# BLDC_MC_Schematic.net
KiCad netlist of a schematic drawn in Altium Designer
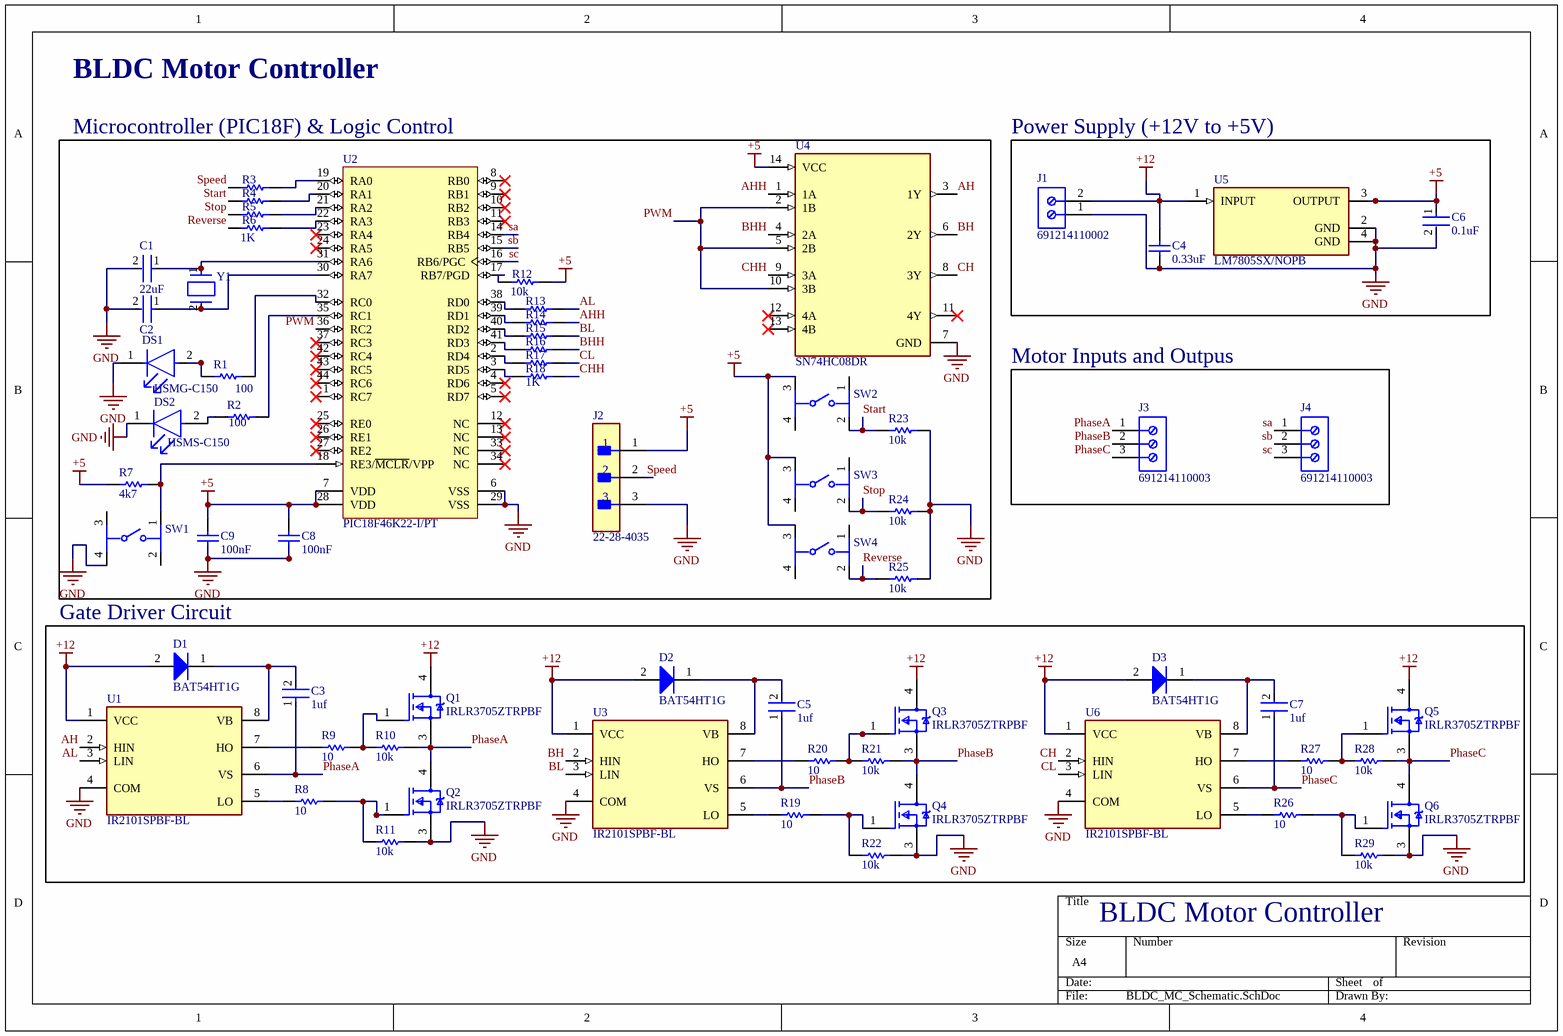
[diagram p0: BLDC_MC_Schematic.SchDoc]

(export (version "E")
  (design (tool "Eeschema 10.0.6"))
  (components
    (comp (ref "C1")
      (value "22uF")
      (footprint "FP-GRM21B-0_15-MFG")
      (description "Chip Multilayer Ceramic Capacitors for General Purpose, 0805, 22uF, X5R, 15%, 20%, 6.3V")
      (fields (field (name "VOLTAGE") "6.3V") (field (name "TOLERANCE") "20%"))
      (libsource (lib "Altium Content Vault") (part "b4654b650e69147ec39a6b967a45e02"))
    )
    (comp (ref "C2")
      (value "22uF")
      (footprint "FP-GRM21B-0_15-MFG")
      (description "Chip Multilayer Ceramic Capacitors for General Purpose, 0805, 22uF, X5R, 15%, 20%, 6.3V")
      (fields (field (name "VOLTAGE") "6.3V") (field (name "TOLERANCE") "20%"))
      (libsource (lib "Altium Content Vault") (part "b4654b650e69147ec39a6b967a45e02"))
    )
    (comp (ref "C3")
      (value "1uf")
      (footprint "FP-GRM55D-0_4-IPC_A")
      (description "Chip Multilayer Ceramic Capacitors for General Purpose, 2220, 1.0uF, X7R, 15%, 10%, 250V")
      (fields (field (name "VOLTAGE") "250V") (field (name "TOLERANCE") "10%"))
      (libsource (lib "Altium Content Vault") (part "b4654b650e69147ec39a6b967a45e02"))
    )
    (comp (ref "C4")
      (value "0.33uF")
      (footprint "CAPC1005X55X25ML05T10")
      (fields (field (name "PART NUMBER") "GRM155R61A334KE15D") (field (name "MANUFACTURER") "Murata"))
      (libsource (lib "Altium Content Vault") (part "CAP"))
    )
    (comp (ref "C5")
      (value "1uf")
      (footprint "FP-GRM55D-0_4-IPC_A")
      (description "Chip Multilayer Ceramic Capacitors for General Purpose, 2220, 1.0uF, X7R, 15%, 10%, 250V")
      (fields (field (name "VOLTAGE") "250V") (field (name "TOLERANCE") "10%"))
      (libsource (lib "Altium Content Vault") (part "b4654b650e69147ec39a6b967a45e02"))
    )
    (comp (ref "C6")
      (value "0.1uF")
      (footprint "FP-C1005-050-0_05-IPC_C")
      (description "Multilayer Ceramic Capacitors 100nF ±10% 50V X7R SMD 0402")
      (fields (field (name "VOLTAGE") "50V") (field (name "TOLERANCE") "10%"))
      (libsource (lib "Altium Content Vault") (part "b4654b650e69147ec39a6b967a45e02"))
    )
    (comp (ref "C7")
      (value "1uf")
      (footprint "FP-GRM55D-0_4-IPC_A")
      (description "Chip Multilayer Ceramic Capacitors for General Purpose, 2220, 1.0uF, X7R, 15%, 10%, 250V")
      (fields (field (name "VOLTAGE") "250V") (field (name "TOLERANCE") "10%"))
      (libsource (lib "Altium Content Vault") (part "b4654b650e69147ec39a6b967a45e02"))
    )
    (comp (ref "C8")
      (value "100nF")
      (footprint "CAPC1005X56X25ML10T15")
      (fields
        (field (name "MANUFACTURER") "AVX Interconnect / Elco")
        (field (name "PART NUMBER") "0402YG104ZAT2A")
      )
      (libsource (lib "Altium Content Vault") (part "CAP"))
    )
    (comp (ref "C9")
      (value "100nF")
      (footprint "CAPC1005X56X25ML10T15")
      (fields
        (field (name "MANUFACTURER") "AVX Interconnect / Elco")
        (field (name "PART NUMBER") "0402YG104ZAT2A")
      )
      (libsource (lib "Altium Content Vault") (part "CAP"))
    )
    (comp (ref "D1")
      (value "BAT54HT1G")
      (footprint "ONSC-SOD-323-2-477-02_V")
      (description "Schottky Barrier Diode, 2-Pin SOD-323, Pb-Free, Tape and Reel")
      (fields (field (name "MANUFACTURER") "On Semiconductor"))
      (libsource (lib "Altium Content Vault") (part "ONSC-D-K1A2-2"))
    )
    (comp (ref "D2")
      (value "BAT54HT1G")
      (footprint "ONSC-SOD-323-2-477-02_V")
      (description "Schottky Barrier Diode, 2-Pin SOD-323, Pb-Free, Tape and Reel")
      (fields (field (name "MANUFACTURER") "On Semiconductor"))
      (libsource (lib "Altium Content Vault") (part "ONSC-D-K1A2-2"))
    )
    (comp (ref "D3")
      (value "BAT54HT1G")
      (footprint "ONSC-SOD-323-2-477-02_V")
      (description "Schottky Barrier Diode, 2-Pin SOD-323, Pb-Free, Tape and Reel")
      (fields (field (name "MANUFACTURER") "On Semiconductor"))
      (libsource (lib "Altium Content Vault") (part "ONSC-D-K1A2-2"))
    )
    (comp (ref "DS1")
      (value "HSMG-C150")
      (footprint "FP-HSMG-C150-MFG")
      (description "LED GREEN DIFFUSED 1206 SMD")
      (fields
        (field (name "MANUFACTURER") "Broadcom")
        (field (name "OCTOPART") "https://octopart.com/hsmg-c150-broadcom-71131304")
      )
      (libsource (lib "Altium Content Vault") (part "8706943c75ba83719d021d2fdc84c58"))
    )
    (comp (ref "DS2")
      (value "HSMS-C150")
      (footprint "FP-HSMS-C150-MFG")
      (description "LED RED DIFFUSED CHIP SMD")
      (libsource (lib "Altium Content Vault") (part "8706943c75ba83719d021d2fdc84c58"))
    )
    (comp (ref "J1")
      (value "691214110002")
      (footprint "691214110002")
      (fields (field (name "VOLTAGE") "300V"))
      (libsource (lib "Altium Content Vault") (part "TBL - 1R - 02P - Screw"))
    )
    (comp (ref "J2")
      (value "22-28-4035")
      (footprint "FP-22-28-4035-MFG")
      (libsource (lib "Altium Content Vault") (part "0d3f023dd272f625e17a2be33dea85f"))
    )
    (comp (ref "J3")
      (value "691214110003")
      (footprint "691214110003")
      (fields (field (name "VOLTAGE") "300V"))
      (libsource (lib "Altium Content Vault") (part "TBL - 1R - 03P - Screw"))
    )
    (comp (ref "J4")
      (value "691214110003")
      (footprint "691214110003")
      (fields (field (name "VOLTAGE") "300V"))
      (libsource (lib "Altium Content Vault") (part "TBL - 1R - 03P - Screw"))
    )
    (comp (ref "Q1")
      (value "IRLR3705ZTRPBF")
      (footprint "FP-PG-TO252-3-MFG")
      (description "MOSFET N-CH 55V 42A DPAK")
      (fields (field (name "OCTOPART") "https://octopart.com/irlr3705ztrpbf-infineon-65875040"))
      (libsource (lib "Altium Content Vault") (part "e748bc7c0bda14637a9f13d1d571a93"))
    )
    (comp (ref "Q2")
      (value "IRLR3705ZTRPBF")
      (footprint "FP-PG-TO252-3-MFG")
      (description "MOSFET N-CH 55V 42A DPAK")
      (fields (field (name "OCTOPART") "https://octopart.com/irlr3705ztrpbf-infineon-65875040"))
      (libsource (lib "Altium Content Vault") (part "e748bc7c0bda14637a9f13d1d571a93"))
    )
    (comp (ref "Q3")
      (value "IRLR3705ZTRPBF")
      (footprint "FP-PG-TO252-3-MFG")
      (description "MOSFET N-CH 55V 42A DPAK")
      (fields (field (name "OCTOPART") "https://octopart.com/irlr3705ztrpbf-infineon-65875040"))
      (libsource (lib "Altium Content Vault") (part "e748bc7c0bda14637a9f13d1d571a93"))
    )
    (comp (ref "Q4")
      (value "IRLR3705ZTRPBF")
      (footprint "FP-PG-TO252-3-MFG")
      (description "MOSFET N-CH 55V 42A DPAK")
      (fields (field (name "OCTOPART") "https://octopart.com/irlr3705ztrpbf-infineon-65875040"))
      (libsource (lib "Altium Content Vault") (part "e748bc7c0bda14637a9f13d1d571a93"))
    )
    (comp (ref "Q5")
      (value "IRLR3705ZTRPBF")
      (footprint "FP-PG-TO252-3-MFG")
      (description "MOSFET N-CH 55V 42A DPAK")
      (fields (field (name "OCTOPART") "https://octopart.com/irlr3705ztrpbf-infineon-65875040"))
      (libsource (lib "Altium Content Vault") (part "e748bc7c0bda14637a9f13d1d571a93"))
    )
    (comp (ref "Q6")
      (value "IRLR3705ZTRPBF")
      (footprint "FP-PG-TO252-3-MFG")
      (description "MOSFET N-CH 55V 42A DPAK")
      (fields (field (name "OCTOPART") "https://octopart.com/irlr3705ztrpbf-infineon-65875040"))
      (libsource (lib "Altium Content Vault") (part "e748bc7c0bda14637a9f13d1d571a93"))
    )
    (comp (ref "R1")
      (value "100")
      (footprint "RESC1608X55X30LL15T15")
      (fields (field (name "MANUFACTURER") "Panasonic") (field (name "PART NUMBER") "ERJ-3EKF1000V"))
      (libsource (lib "Altium Content Vault") (part "RES"))
    )
    (comp (ref "R2")
      (value "100")
      (footprint "RESC1608X55X30LL15T15")
      (fields (field (name "MANUFACTURER") "Panasonic") (field (name "PART NUMBER") "ERJ-3EKF1000V"))
      (libsource (lib "Altium Content Vault") (part "RES"))
    )
    (comp (ref "R3")
      (value "1K")
      (footprint "RESC1608X55X30LL15T15")
      (fields (field (name "PART NUMBER") "ERJ-3EKF1001V") (field (name "MANUFACTURER") "Panasonic"))
      (libsource (lib "Altium Content Vault") (part "RES"))
    )
    (comp (ref "R4")
      (value "1K")
      (footprint "RESC1608X55X30LL15T15")
      (fields (field (name "PART NUMBER") "ERJ-3EKF1001V") (field (name "MANUFACTURER") "Panasonic"))
      (libsource (lib "Altium Content Vault") (part "RES"))
    )
    (comp (ref "R5")
      (value "1K")
      (footprint "RESC1608X55X30LL15T15")
      (fields (field (name "PART NUMBER") "ERJ-3EKF1001V") (field (name "MANUFACTURER") "Panasonic"))
      (libsource (lib "Altium Content Vault") (part "RES"))
    )
    (comp (ref "R6")
      (value "1K")
      (footprint "RESC1608X55X30LL15T15")
      (fields (field (name "PART NUMBER") "ERJ-3EKF1001V") (field (name "MANUFACTURER") "Panasonic"))
      (libsource (lib "Altium Content Vault") (part "RES"))
    )
    (comp (ref "R7")
      (value "4k7")
      (footprint "RESC1005X40X25LL05T05")
      (description "Chip Resistor, 4.7 KOhm, +/- 1%, 0.1 W, -55 to 155 degC, 0402 (1005 Metric), RoHS, Tape and Reel")
      (fields (field (name "TOLERANCE") "1%") (field (name "PARTNUMBER") "ERJ-2RKF4701X"))
      (libsource (lib "Altium Content Vault") (part "RES-2"))
    )
    (comp (ref "R8")
      (value "10")
      (footprint "RESC2013X50X30NL20T20")
      (fields (field (name "MANUFACTURER") "Vishay Dale") (field (name "PART NUMBER") "CRCW080510R0FKEA"))
      (libsource (lib "Altium Content Vault") (part "RES"))
    )
    (comp (ref "R9")
      (value "10")
      (footprint "RESC2013X50X30NL20T20")
      (fields (field (name "MANUFACTURER") "Vishay Dale") (field (name "PART NUMBER") "CRCW080510R0FKEA"))
      (libsource (lib "Altium Content Vault") (part "RES"))
    )
    (comp (ref "R10")
      (value "10k")
      (footprint "RESC1609X50X30NL8T20")
      (description "Chip Resistor, 10 KOhm, +/- 1%, 100 mW, -55 to 155 degC, 0603 (1608 Metric), RoHS, Tape and Reel")
      (fields (field (name "MANUFACTURER") "Vishay Semiconductor"))
      (libsource (lib "Altium Content Vault") (part "RES-2"))
    )
    (comp (ref "R11")
      (value "10k")
      (footprint "RESC1609X50X30NL8T20")
      (description "Chip Resistor, 10 KOhm, +/- 1%, 100 mW, -55 to 155 degC, 0603 (1608 Metric), RoHS, Tape and Reel")
      (fields (field (name "MANUFACTURER") "Vishay Semiconductor"))
      (libsource (lib "Altium Content Vault") (part "RES-2"))
    )
    (comp (ref "R12")
      (value "10k")
      (footprint "RESC1609X50X30NL8T20")
      (description "Chip Resistor, 10 KOhm, +/- 1%, 100 mW, -55 to 155 degC, 0603 (1608 Metric), RoHS, Tape and Reel")
      (fields (field (name "MANUFACTURER") "Vishay Semiconductor"))
      (libsource (lib "Altium Content Vault") (part "RES-2"))
    )
    (comp (ref "R13")
      (value "1K")
      (footprint "RESC1608X55X30LL15T15")
      (fields (field (name "PART NUMBER") "ERJ-3EKF1001V") (field (name "MANUFACTURER") "Panasonic"))
      (libsource (lib "Altium Content Vault") (part "RES"))
    )
    (comp (ref "R14")
      (value "1K")
      (footprint "RESC1608X55X30LL15T15")
      (fields (field (name "PART NUMBER") "ERJ-3EKF1001V") (field (name "MANUFACTURER") "Panasonic"))
      (libsource (lib "Altium Content Vault") (part "RES"))
    )
    (comp (ref "R15")
      (value "1K")
      (footprint "RESC1608X55X30LL15T15")
      (fields (field (name "PART NUMBER") "ERJ-3EKF1001V") (field (name "MANUFACTURER") "Panasonic"))
      (libsource (lib "Altium Content Vault") (part "RES"))
    )
    (comp (ref "R16")
      (value "1K")
      (footprint "RESC1608X55X30LL15T15")
      (fields (field (name "PART NUMBER") "ERJ-3EKF1001V") (field (name "MANUFACTURER") "Panasonic"))
      (libsource (lib "Altium Content Vault") (part "RES"))
    )
    (comp (ref "R17")
      (value "1K")
      (footprint "RESC1608X55X30LL15T15")
      (fields (field (name "PART NUMBER") "ERJ-3EKF1001V") (field (name "MANUFACTURER") "Panasonic"))
      (libsource (lib "Altium Content Vault") (part "RES"))
    )
    (comp (ref "R18")
      (value "1K")
      (footprint "RESC1608X55X30LL15T15")
      (fields (field (name "PART NUMBER") "ERJ-3EKF1001V") (field (name "MANUFACTURER") "Panasonic"))
      (libsource (lib "Altium Content Vault") (part "RES"))
    )
    (comp (ref "R19")
      (value "10")
      (footprint "RESC2013X50X30NL20T20")
      (fields (field (name "MANUFACTURER") "Vishay Dale") (field (name "PART NUMBER") "CRCW080510R0FKEA"))
      (libsource (lib "Altium Content Vault") (part "RES"))
    )
    (comp (ref "R20")
      (value "10")
      (footprint "RESC2013X50X30NL20T20")
      (fields (field (name "MANUFACTURER") "Vishay Dale") (field (name "PART NUMBER") "CRCW080510R0FKEA"))
      (libsource (lib "Altium Content Vault") (part "RES"))
    )
    (comp (ref "R21")
      (value "10k")
      (footprint "RESC1609X50X30NL8T20")
      (description "Chip Resistor, 10 KOhm, +/- 1%, 100 mW, -55 to 155 degC, 0603 (1608 Metric), RoHS, Tape and Reel")
      (fields (field (name "MANUFACTURER") "Vishay Semiconductor"))
      (libsource (lib "Altium Content Vault") (part "RES-2"))
    )
    (comp (ref "R22")
      (value "10k")
      (footprint "RESC1609X50X30NL8T20")
      (description "Chip Resistor, 10 KOhm, +/- 1%, 100 mW, -55 to 155 degC, 0603 (1608 Metric), RoHS, Tape and Reel")
      (fields (field (name "MANUFACTURER") "Vishay Semiconductor"))
      (libsource (lib "Altium Content Vault") (part "RES-2"))
    )
    (comp (ref "R23")
      (value "10k")
      (footprint "RESC1609X50X30NL8T20")
      (description "Chip Resistor, 10 KOhm, +/- 1%, 100 mW, -55 to 155 degC, 0603 (1608 Metric), RoHS, Tape and Reel")
      (fields (field (name "MANUFACTURER") "Vishay Semiconductor"))
      (libsource (lib "Altium Content Vault") (part "RES-2"))
    )
    (comp (ref "R24")
      (value "10k")
      (footprint "RESC1609X50X30NL8T20")
      (description "Chip Resistor, 10 KOhm, +/- 1%, 100 mW, -55 to 155 degC, 0603 (1608 Metric), RoHS, Tape and Reel")
      (fields (field (name "MANUFACTURER") "Vishay Semiconductor"))
      (libsource (lib "Altium Content Vault") (part "RES-2"))
    )
    (comp (ref "R25")
      (value "10k")
      (footprint "RESC1609X50X30NL8T20")
      (description "Chip Resistor, 10 KOhm, +/- 1%, 100 mW, -55 to 155 degC, 0603 (1608 Metric), RoHS, Tape and Reel")
      (fields (field (name "MANUFACTURER") "Vishay Semiconductor"))
      (libsource (lib "Altium Content Vault") (part "RES-2"))
    )
    (comp (ref "R26")
      (value "10")
      (footprint "RESC2013X50X30NL20T20")
      (fields (field (name "MANUFACTURER") "Vishay Dale") (field (name "PART NUMBER") "CRCW080510R0FKEA"))
      (libsource (lib "Altium Content Vault") (part "RES"))
    )
    (comp (ref "R27")
      (value "10")
      (footprint "RESC2013X50X30NL20T20")
      (fields (field (name "MANUFACTURER") "Vishay Dale") (field (name "PART NUMBER") "CRCW080510R0FKEA"))
      (libsource (lib "Altium Content Vault") (part "RES"))
    )
    (comp (ref "R28")
      (value "10k")
      (footprint "RESC1609X50X30NL8T20")
      (description "Chip Resistor, 10 KOhm, +/- 1%, 100 mW, -55 to 155 degC, 0603 (1608 Metric), RoHS, Tape and Reel")
      (fields (field (name "MANUFACTURER") "Vishay Semiconductor"))
      (libsource (lib "Altium Content Vault") (part "RES-2"))
    )
    (comp (ref "R29")
      (value "10k")
      (footprint "RESC1609X50X30NL8T20")
      (description "Chip Resistor, 10 KOhm, +/- 1%, 100 mW, -55 to 155 degC, 0603 (1608 Metric), RoHS, Tape and Reel")
      (fields (field (name "MANUFACTURER") "Vishay Semiconductor"))
      (libsource (lib "Altium Content Vault") (part "RES-2"))
    )
    (comp (ref "SW1")
      (value "PTS810SJM250SMTRLFS")
      (footprint "FP-PTS810SJM250SMTRLFS-MFG")
      (description "SWITCH TACTILE SPST-NO 0.05A 16V")
      (libsource (lib "Altium Content Vault") (part "1adf0dd01260c80cf25a44bfd6b99ba"))
    )
    (comp (ref "SW2")
      (value "PTS810SJM250SMTRLFS")
      (footprint "FP-PTS810SJM250SMTRLFS-MFG")
      (description "SWITCH TACTILE SPST-NO 0.05A 16V")
      (libsource (lib "Altium Content Vault") (part "1adf0dd01260c80cf25a44bfd6b99ba"))
    )
    (comp (ref "SW3")
      (value "PTS810SJM250SMTRLFS")
      (footprint "FP-PTS810SJM250SMTRLFS-MFG")
      (description "SWITCH TACTILE SPST-NO 0.05A 16V")
      (libsource (lib "Altium Content Vault") (part "1adf0dd01260c80cf25a44bfd6b99ba"))
    )
    (comp (ref "SW4")
      (value "PTS810SJM250SMTRLFS")
      (footprint "FP-PTS810SJM250SMTRLFS-MFG")
      (description "SWITCH TACTILE SPST-NO 0.05A 16V")
      (libsource (lib "Altium Content Vault") (part "1adf0dd01260c80cf25a44bfd6b99ba"))
    )
    (comp (ref "U1")
      (value "IR2101SPBF-BL")
      (footprint "FP-PG-DSO-8-IPC_B")
      (description "MOSFET DRVR 600V 0.36A 2-OUT Hi/Lo Side Non-Inv 8-Pin SOIC")
      (libsource (lib "Altium Content Vault") (part "434b8f4246b9711489e8709b290a301"))
    )
    (comp (ref "U2")
      (value "PIC18F46K22-I/PT")
      (footprint "MCHP-TQFP-PT44_L")
      (fields (field (name "MANUFACTURER") "Microchip"))
      (libsource (lib "Altium Content Vault") (part "MCHP-PIC18F4XK22-TQFP-44"))
    )
    (comp (ref "U3")
      (value "IR2101SPBF-BL")
      (footprint "FP-PG-DSO-8-IPC_B")
      (description "MOSFET DRVR 600V 0.36A 2-OUT Hi/Lo Side Non-Inv 8-Pin SOIC")
      (libsource (lib "Altium Content Vault") (part "434b8f4246b9711489e8709b290a301"))
    )
    (comp (ref "U4")
      (value "SN74HC08DR")
      (footprint "FP-D0014A-MFG")
      (description "IC GATE AND 4CH 2-INP 14SOIC")
      (libsource (lib "Altium Content Vault") (part "882a680e930cee923804cf82774a10f"))
    )
    (comp (ref "U5")
      (value "LM7805SX/NOPB")
      (footprint "FP-KTT0003B-MFG")
      (description "IC REG LIN 5V 1.5A DDPAK/TO263-3")
      (fields
        (field (name "OCTOPART") "https://octopart.com/lm7805sx%2Fnopb-texas+instruments-74629994")
        (field (name "MANUFACTURER") "Texas Instruments")
      )
      (libsource (lib "Altium Content Vault") (part "bbc5c6f8b1069d3695ea5b916bb48f2"))
    )
    (comp (ref "U6")
      (value "IR2101SPBF-BL")
      (footprint "FP-PG-DSO-8-IPC_B")
      (description "MOSFET DRVR 600V 0.36A 2-OUT Hi/Lo Side Non-Inv 8-Pin SOIC")
      (libsource (lib "Altium Content Vault") (part "434b8f4246b9711489e8709b290a301"))
    )
    (comp (ref "Y1")
      (value "ABM7-16.000MHZ-D2Y-T")
      (footprint "FP-ABM7-MFG")
      (description "Crystal 16MHz ±20ppm 18pF SMD-2 6mm x 3.5mm")
      (fields (field (name "TOLERANCE") "20ppm"))
      (libsource (lib "Altium Content Vault") (part "c23a69dc6c9e2f18f2079038eb95dd1"))
    )
  )
  (nets
    (net (code "1") (name "+5") (class "Default")
      (node (ref "C6") (pin "1") (pinfunction "1_1") (pintype "passive"))
      (node (ref "C8") (pin "2") (pinfunction "2_2") (pintype "passive"))
      (node (ref "C9") (pin "2") (pinfunction "2_2") (pintype "passive"))
      (node (ref "J2") (pin "1") (pinfunction "1_1") (pintype "passive"))
      (node (ref "R12") (pin "2") (pinfunction "2_2") (pintype "passive"))
      (node (ref "R7") (pin "1") (pinfunction "1_1") (pintype "passive"))
      (node (ref "SW2") (pin "3") (pinfunction "3_3") (pintype "passive"))
      (node (ref "SW3") (pin "3") (pinfunction "3_3") (pintype "passive"))
      (node (ref "SW4") (pin "3") (pinfunction "3_3") (pintype "passive"))
      (node (ref "U2") (pin "28") (pinfunction "VDD_28") (pintype "power_in"))
      (node (ref "U2") (pin "7") (pinfunction "VDD_7") (pintype "power_in"))
      (node (ref "U4") (pin "14") (pinfunction "VCC_14") (pintype "input"))
      (node (ref "U5") (pin "3") (pinfunction "OUTPUT_3") (pintype "power_in"))
    )
    (net (code "2") (name "+12") (class "Default")
      (node (ref "C4") (pin "2") (pinfunction "2_2") (pintype "passive"))
      (node (ref "D1") (pin "2") (pinfunction "A_2") (pintype "passive"))
      (node (ref "D2") (pin "2") (pinfunction "A_2") (pintype "passive"))
      (node (ref "D3") (pin "2") (pinfunction "A_2") (pintype "passive"))
      (node (ref "J1") (pin "2") (pinfunction "2_2") (pintype "passive"))
      (node (ref "Q1") (pin "4") (pinfunction "DRAIN_4") (pintype "passive"))
      (node (ref "Q3") (pin "4") (pinfunction "DRAIN_4") (pintype "passive"))
      (node (ref "Q5") (pin "4") (pinfunction "DRAIN_4") (pintype "passive"))
      (node (ref "U1") (pin "1") (pinfunction "VCC_1") (pintype "power_in"))
      (node (ref "U3") (pin "1") (pinfunction "VCC_1") (pintype "power_in"))
      (node (ref "U5") (pin "1") (pinfunction "INPUT_1") (pintype "input"))
      (node (ref "U6") (pin "1") (pinfunction "VCC_1") (pintype "power_in"))
    )
    (net (code "3") (name "/AH") (class "Default")
      (node (ref "U1") (pin "2") (pinfunction "HIN_2") (pintype "input"))
      (node (ref "U4") (pin "3") (pinfunction "1Y_3") (pintype "output"))
    )
    (net (code "4") (name "/AHH") (class "Default")
      (node (ref "R14") (pin "2") (pinfunction "2_2") (pintype "passive"))
      (node (ref "U4") (pin "1") (pinfunction "1A_1") (pintype "input"))
    )
    (net (code "5") (name "/AL") (class "Default")
      (node (ref "R13") (pin "2") (pinfunction "2_2") (pintype "passive"))
      (node (ref "U1") (pin "3") (pinfunction "LIN_3") (pintype "input"))
    )
    (net (code "6") (name "/BH") (class "Default")
      (node (ref "U3") (pin "2") (pinfunction "HIN_2") (pintype "input"))
      (node (ref "U4") (pin "6") (pinfunction "2Y_6") (pintype "output"))
    )
    (net (code "7") (name "/BHH") (class "Default")
      (node (ref "R16") (pin "2") (pinfunction "2_2") (pintype "passive"))
      (node (ref "U4") (pin "4") (pinfunction "2A_4") (pintype "input"))
    )
    (net (code "8") (name "/BL") (class "Default")
      (node (ref "R15") (pin "2") (pinfunction "2_2") (pintype "passive"))
      (node (ref "U3") (pin "3") (pinfunction "LIN_3") (pintype "input"))
    )
    (net (code "9") (name "/CH") (class "Default")
      (node (ref "U4") (pin "8") (pinfunction "3Y_8") (pintype "output"))
      (node (ref "U6") (pin "2") (pinfunction "HIN_2") (pintype "input"))
    )
    (net (code "10") (name "/CHH") (class "Default")
      (node (ref "R18") (pin "2") (pinfunction "2_2") (pintype "passive"))
      (node (ref "U4") (pin "9") (pinfunction "3A_9") (pintype "input"))
    )
    (net (code "11") (name "/CL") (class "Default")
      (node (ref "R17") (pin "2") (pinfunction "2_2") (pintype "passive"))
      (node (ref "U6") (pin "3") (pinfunction "LIN_3") (pintype "input"))
    )
    (net (code "12") (name "/PWM") (class "Default")
      (node (ref "U2") (pin "36") (pinfunction "RC2_36") (pintype "bidirectional"))
      (node (ref "U4") (pin "10") (pinfunction "3B_10") (pintype "input"))
      (node (ref "U4") (pin "2") (pinfunction "1B_2") (pintype "input"))
      (node (ref "U4") (pin "5") (pinfunction "2B_5") (pintype "input"))
    )
    (net (code "13") (name "/PhaseA") (class "Default")
      (node (ref "C3") (pin "1") (pinfunction "1_1") (pintype "passive"))
      (node (ref "J3") (pin "1") (pinfunction "1_1") (pintype "passive"))
      (node (ref "Q1") (pin "3") (pinfunction "SOURCE_3") (pintype "passive"))
      (node (ref "Q2") (pin "4") (pinfunction "DRAIN_4") (pintype "passive"))
      (node (ref "R10") (pin "2") (pinfunction "2_2") (pintype "passive"))
      (node (ref "U1") (pin "6") (pinfunction "VS_6") (pintype "power_in"))
    )
    (net (code "14") (name "/PhaseB") (class "Default")
      (node (ref "C5") (pin "1") (pinfunction "1_1") (pintype "passive"))
      (node (ref "J3") (pin "2") (pinfunction "2_2") (pintype "passive"))
      (node (ref "Q3") (pin "3") (pinfunction "SOURCE_3") (pintype "passive"))
      (node (ref "Q4") (pin "4") (pinfunction "DRAIN_4") (pintype "passive"))
      (node (ref "R21") (pin "2") (pinfunction "2_2") (pintype "passive"))
      (node (ref "U3") (pin "6") (pinfunction "VS_6") (pintype "power_in"))
    )
    (net (code "15") (name "/PhaseC") (class "Default")
      (node (ref "C7") (pin "1") (pinfunction "1_1") (pintype "passive"))
      (node (ref "J3") (pin "3") (pinfunction "3_3") (pintype "passive"))
      (node (ref "Q5") (pin "3") (pinfunction "SOURCE_3") (pintype "passive"))
      (node (ref "Q6") (pin "4") (pinfunction "DRAIN_4") (pintype "passive"))
      (node (ref "R28") (pin "2") (pinfunction "2_2") (pintype "passive"))
      (node (ref "U6") (pin "6") (pinfunction "VS_6") (pintype "power_in"))
    )
    (net (code "16") (name "/Reverse") (class "Default")
      (node (ref "R25") (pin "1") (pinfunction "1_1") (pintype "passive"))
      (node (ref "R6") (pin "1") (pinfunction "1_1") (pintype "passive"))
      (node (ref "SW4") (pin "2") (pinfunction "2_2") (pintype "passive"))
    )
    (net (code "17") (name "/Speed") (class "Default")
      (node (ref "J2") (pin "2") (pinfunction "2_2") (pintype "passive"))
      (node (ref "R3") (pin "1") (pinfunction "1_1") (pintype "passive"))
    )
    (net (code "18") (name "/Start") (class "Default")
      (node (ref "R23") (pin "1") (pinfunction "1_1") (pintype "passive"))
      (node (ref "R4") (pin "1") (pinfunction "1_1") (pintype "passive"))
      (node (ref "SW2") (pin "2") (pinfunction "2_2") (pintype "passive"))
    )
    (net (code "19") (name "/Stop") (class "Default")
      (node (ref "R24") (pin "1") (pinfunction "1_1") (pintype "passive"))
      (node (ref "R5") (pin "1") (pinfunction "1_1") (pintype "passive"))
      (node (ref "SW3") (pin "2") (pinfunction "2_2") (pintype "passive"))
    )
    (net (code "20") (name "/sa") (class "Default")
      (node (ref "J4") (pin "1") (pinfunction "1_1") (pintype "passive"))
      (node (ref "U2") (pin "14") (pinfunction "RB4_14") (pintype "bidirectional"))
    )
    (net (code "21") (name "/sb") (class "Default")
      (node (ref "J4") (pin "2") (pinfunction "2_2") (pintype "passive"))
      (node (ref "U2") (pin "15") (pinfunction "RB5_15") (pintype "bidirectional"))
    )
    (net (code "22") (name "/sc") (class "Default")
      (node (ref "J4") (pin "3") (pinfunction "3_3") (pintype "passive"))
      (node (ref "U2") (pin "16") (pinfunction "RB6/PGC_16") (pintype "bidirectional"))
    )
    (net (code "23") (name "GND") (class "Default")
      (node (ref "C1") (pin "2") (pinfunction "2_2") (pintype "passive"))
      (node (ref "C2") (pin "2") (pinfunction "2_2") (pintype "passive"))
      (node (ref "C4") (pin "1") (pinfunction "1_1") (pintype "passive"))
      (node (ref "C6") (pin "2") (pinfunction "2_2") (pintype "passive"))
      (node (ref "C8") (pin "1") (pinfunction "1_1") (pintype "passive"))
      (node (ref "C9") (pin "1") (pinfunction "1_1") (pintype "passive"))
      (node (ref "DS1") (pin "1") (pinfunction "C_1") (pintype "passive"))
      (node (ref "DS2") (pin "1") (pinfunction "C_1") (pintype "passive"))
      (node (ref "J1") (pin "1") (pinfunction "1_1") (pintype "passive"))
      (node (ref "J2") (pin "3") (pinfunction "3_3") (pintype "passive"))
      (node (ref "Q2") (pin "3") (pinfunction "SOURCE_3") (pintype "passive"))
      (node (ref "Q4") (pin "3") (pinfunction "SOURCE_3") (pintype "passive"))
      (node (ref "Q6") (pin "3") (pinfunction "SOURCE_3") (pintype "passive"))
      (node (ref "R11") (pin "2") (pinfunction "2_2") (pintype "passive"))
      (node (ref "R22") (pin "2") (pinfunction "2_2") (pintype "passive"))
      (node (ref "R23") (pin "2") (pinfunction "2_2") (pintype "passive"))
      (node (ref "R24") (pin "2") (pinfunction "2_2") (pintype "passive"))
      (node (ref "R25") (pin "2") (pinfunction "2_2") (pintype "passive"))
      (node (ref "R29") (pin "2") (pinfunction "2_2") (pintype "passive"))
      (node (ref "SW1") (pin "4") (pinfunction "4_4") (pintype "passive"))
      (node (ref "U1") (pin "4") (pinfunction "COM_4") (pintype "passive"))
      (node (ref "U2") (pin "29") (pinfunction "VSS_29") (pintype "power_in"))
      (node (ref "U2") (pin "6") (pinfunction "VSS_6") (pintype "power_in"))
      (node (ref "U3") (pin "4") (pinfunction "COM_4") (pintype "passive"))
      (node (ref "U4") (pin "7") (pinfunction "GND_7") (pintype "power_in"))
      (node (ref "U5") (pin "2") (pinfunction "GND_2") (pintype "power_in"))
      (node (ref "U5") (pin "4") (pinfunction "GND_4") (pintype "power_in"))
      (node (ref "U6") (pin "4") (pinfunction "COM_4") (pintype "passive"))
    )
    (net (code "24") (name "Net-(D1-K)") (class "Default")
      (node (ref "C3") (pin "2") (pinfunction "2_2") (pintype "passive"))
      (node (ref "D1") (pin "1") (pinfunction "K_1") (pintype "passive"))
      (node (ref "U1") (pin "8") (pinfunction "VB_8") (pintype "power_in"))
    )
    (net (code "25") (name "Net-(D2-K)") (class "Default")
      (node (ref "C5") (pin "2") (pinfunction "2_2") (pintype "passive"))
      (node (ref "D2") (pin "1") (pinfunction "K_1") (pintype "passive"))
      (node (ref "U3") (pin "8") (pinfunction "VB_8") (pintype "power_in"))
    )
    (net (code "26") (name "Net-(D3-K)") (class "Default")
      (node (ref "C7") (pin "2") (pinfunction "2_2") (pintype "passive"))
      (node (ref "D3") (pin "1") (pinfunction "K_1") (pintype "passive"))
      (node (ref "U6") (pin "8") (pinfunction "VB_8") (pintype "power_in"))
    )
    (net (code "27") (name "Net-(DS1-A)") (class "Default")
      (node (ref "DS1") (pin "2") (pinfunction "A_2") (pintype "passive"))
      (node (ref "R1") (pin "1") (pinfunction "1_1") (pintype "passive"))
    )
    (net (code "28") (name "Net-(DS2-A)") (class "Default")
      (node (ref "DS2") (pin "2") (pinfunction "A_2") (pintype "passive"))
      (node (ref "R2") (pin "1") (pinfunction "1_1") (pintype "passive"))
    )
    (net (code "29") (name "Net-(Q1-GATE)") (class "Default")
      (node (ref "Q1") (pin "1") (pinfunction "GATE_1") (pintype "passive"))
      (node (ref "R10") (pin "1") (pinfunction "1_1") (pintype "passive"))
      (node (ref "R9") (pin "2") (pinfunction "2_2") (pintype "passive"))
    )
    (net (code "30") (name "Net-(Q2-GATE)") (class "Default")
      (node (ref "Q2") (pin "1") (pinfunction "GATE_1") (pintype "passive"))
      (node (ref "R11") (pin "1") (pinfunction "1_1") (pintype "passive"))
      (node (ref "R8") (pin "2") (pinfunction "2_2") (pintype "passive"))
    )
    (net (code "31") (name "Net-(Q3-GATE)") (class "Default")
      (node (ref "Q3") (pin "1") (pinfunction "GATE_1") (pintype "passive"))
      (node (ref "R20") (pin "2") (pinfunction "2_2") (pintype "passive"))
      (node (ref "R21") (pin "1") (pinfunction "1_1") (pintype "passive"))
    )
    (net (code "32") (name "Net-(Q4-GATE)") (class "Default")
      (node (ref "Q4") (pin "1") (pinfunction "GATE_1") (pintype "passive"))
      (node (ref "R19") (pin "2") (pinfunction "2_2") (pintype "passive"))
      (node (ref "R22") (pin "1") (pinfunction "1_1") (pintype "passive"))
    )
    (net (code "33") (name "Net-(Q5-GATE)") (class "Default")
      (node (ref "Q5") (pin "1") (pinfunction "GATE_1") (pintype "passive"))
      (node (ref "R27") (pin "2") (pinfunction "2_2") (pintype "passive"))
      (node (ref "R28") (pin "1") (pinfunction "1_1") (pintype "passive"))
    )
    (net (code "34") (name "Net-(Q6-GATE)") (class "Default")
      (node (ref "Q6") (pin "1") (pinfunction "GATE_1") (pintype "passive"))
      (node (ref "R26") (pin "2") (pinfunction "2_2") (pintype "passive"))
      (node (ref "R29") (pin "1") (pinfunction "1_1") (pintype "passive"))
    )
    (net (code "35") (name "Net-(U1-HO)") (class "Default")
      (node (ref "R9") (pin "1") (pinfunction "1_1") (pintype "passive"))
      (node (ref "U1") (pin "7") (pinfunction "HO_7") (pintype "passive"))
    )
    (net (code "36") (name "Net-(U1-LO)") (class "Default")
      (node (ref "R8") (pin "1") (pinfunction "1_1") (pintype "passive"))
      (node (ref "U1") (pin "5") (pinfunction "LO_5") (pintype "passive"))
    )
    (net (code "37") (name "Net-(U2-RA0)") (class "Default")
      (node (ref "R3") (pin "2") (pinfunction "2_2") (pintype "passive"))
      (node (ref "U2") (pin "19") (pinfunction "RA0_19") (pintype "bidirectional"))
    )
    (net (code "38") (name "Net-(U2-RA1)") (class "Default")
      (node (ref "R4") (pin "2") (pinfunction "2_2") (pintype "passive"))
      (node (ref "U2") (pin "20") (pinfunction "RA1_20") (pintype "bidirectional"))
    )
    (net (code "39") (name "Net-(U2-RA2)") (class "Default")
      (node (ref "R5") (pin "2") (pinfunction "2_2") (pintype "passive"))
      (node (ref "U2") (pin "21") (pinfunction "RA2_21") (pintype "bidirectional"))
    )
    (net (code "40") (name "Net-(U2-RA3)") (class "Default")
      (node (ref "R6") (pin "2") (pinfunction "2_2") (pintype "passive"))
      (node (ref "U2") (pin "22") (pinfunction "RA3_22") (pintype "bidirectional"))
    )
    (net (code "41") (name "Net-(U2-RA6)") (class "Default")
      (node (ref "C1") (pin "1") (pinfunction "1_1") (pintype "passive"))
      (node (ref "U2") (pin "31") (pinfunction "RA6_31") (pintype "bidirectional"))
      (node (ref "Y1") (pin "1") (pinfunction "1_1") (pintype "passive"))
    )
    (net (code "42") (name "Net-(U2-RA7)") (class "Default")
      (node (ref "C2") (pin "1") (pinfunction "1_1") (pintype "passive"))
      (node (ref "U2") (pin "30") (pinfunction "RA7_30") (pintype "bidirectional"))
      (node (ref "Y1") (pin "2") (pinfunction "2_2") (pintype "passive"))
    )
    (net (code "43") (name "Net-(U2-RB7{slash}PGD)") (class "Default")
      (node (ref "R12") (pin "1") (pinfunction "1_1") (pintype "passive"))
      (node (ref "U2") (pin "17") (pinfunction "RB7/PGD_17") (pintype "bidirectional"))
    )
    (net (code "44") (name "Net-(U2-RC0)") (class "Default")
      (node (ref "R1") (pin "2") (pinfunction "2_2") (pintype "passive"))
      (node (ref "U2") (pin "32") (pinfunction "RC0_32") (pintype "bidirectional"))
    )
    (net (code "45") (name "Net-(U2-RC1)") (class "Default")
      (node (ref "R2") (pin "2") (pinfunction "2_2") (pintype "passive"))
      (node (ref "U2") (pin "35") (pinfunction "RC1_35") (pintype "bidirectional"))
    )
    (net (code "46") (name "Net-(U2-RD0)") (class "Default")
      (node (ref "R13") (pin "1") (pinfunction "1_1") (pintype "passive"))
      (node (ref "U2") (pin "38") (pinfunction "RD0_38") (pintype "bidirectional"))
    )
    (net (code "47") (name "Net-(U2-RD1)") (class "Default")
      (node (ref "R14") (pin "1") (pinfunction "1_1") (pintype "passive"))
      (node (ref "U2") (pin "39") (pinfunction "RD1_39") (pintype "bidirectional"))
    )
    (net (code "48") (name "Net-(U2-RD2)") (class "Default")
      (node (ref "R15") (pin "1") (pinfunction "1_1") (pintype "passive"))
      (node (ref "U2") (pin "40") (pinfunction "RD2_40") (pintype "bidirectional"))
    )
    (net (code "49") (name "Net-(U2-RD3)") (class "Default")
      (node (ref "R16") (pin "1") (pinfunction "1_1") (pintype "passive"))
      (node (ref "U2") (pin "41") (pinfunction "RD3_41") (pintype "bidirectional"))
    )
    (net (code "50") (name "Net-(U2-RD4)") (class "Default")
      (node (ref "R17") (pin "1") (pinfunction "1_1") (pintype "passive"))
      (node (ref "U2") (pin "2") (pinfunction "RD4_2") (pintype "bidirectional"))
    )
    (net (code "51") (name "Net-(U2-RD5)") (class "Default")
      (node (ref "R18") (pin "1") (pinfunction "1_1") (pintype "passive"))
      (node (ref "U2") (pin "3") (pinfunction "RD5_3") (pintype "bidirectional"))
    )
    (net (code "52") (name "Net-(U2-RE3{slash}~{MCLR}{slash}VPP)") (class "Default")
      (node (ref "R7") (pin "2") (pinfunction "2_2") (pintype "passive"))
      (node (ref "SW1") (pin "1") (pinfunction "1_1") (pintype "passive"))
      (node (ref "U2") (pin "18") (pinfunction "RE3/~{MCLR}/VPP_18") (pintype "input"))
    )
    (net (code "53") (name "Net-(U3-HO)") (class "Default")
      (node (ref "R20") (pin "1") (pinfunction "1_1") (pintype "passive"))
      (node (ref "U3") (pin "7") (pinfunction "HO_7") (pintype "passive"))
    )
    (net (code "54") (name "Net-(U3-LO)") (class "Default")
      (node (ref "R19") (pin "1") (pinfunction "1_1") (pintype "passive"))
      (node (ref "U3") (pin "5") (pinfunction "LO_5") (pintype "passive"))
    )
    (net (code "55") (name "Net-(U6-HO)") (class "Default")
      (node (ref "R27") (pin "1") (pinfunction "1_1") (pintype "passive"))
      (node (ref "U6") (pin "7") (pinfunction "HO_7") (pintype "passive"))
    )
    (net (code "56") (name "Net-(U6-LO)") (class "Default")
      (node (ref "R26") (pin "1") (pinfunction "1_1") (pintype "passive"))
      (node (ref "U6") (pin "5") (pinfunction "LO_5") (pintype "passive"))
    )
    (net (code "57") (name "unconnected-(SW1-Pad2)") (class "Default")
      (node (ref "SW1") (pin "2") (pinfunction "2_2") (pintype "passive"))
    )
    (net (code "58") (name "unconnected-(SW1-Pad3)") (class "Default")
      (node (ref "SW1") (pin "3") (pinfunction "3_3") (pintype "passive"))
    )
    (net (code "59") (name "unconnected-(SW2-Pad1)") (class "Default")
      (node (ref "SW2") (pin "1") (pinfunction "1_1") (pintype "passive"))
    )
    (net (code "60") (name "unconnected-(SW2-Pad4)") (class "Default")
      (node (ref "SW2") (pin "4") (pinfunction "4_4") (pintype "passive"))
    )
    (net (code "61") (name "unconnected-(SW3-Pad1)") (class "Default")
      (node (ref "SW3") (pin "1") (pinfunction "1_1") (pintype "passive"))
    )
    (net (code "62") (name "unconnected-(SW3-Pad4)") (class "Default")
      (node (ref "SW3") (pin "4") (pinfunction "4_4") (pintype "passive"))
    )
    (net (code "63") (name "unconnected-(SW4-Pad1)") (class "Default")
      (node (ref "SW4") (pin "1") (pinfunction "1_1") (pintype "passive"))
    )
    (net (code "64") (name "unconnected-(SW4-Pad4)") (class "Default")
      (node (ref "SW4") (pin "4") (pinfunction "4_4") (pintype "passive"))
    )
    (net (code "65") (name "unconnected-(U2-NC-Pad12)") (class "Default")
      (node (ref "U2") (pin "12") (pinfunction "NC_12") (pintype "passive+no_connect"))
    )
    (net (code "66") (name "unconnected-(U2-NC-Pad13)") (class "Default")
      (node (ref "U2") (pin "13") (pinfunction "NC_13") (pintype "passive+no_connect"))
    )
    (net (code "67") (name "unconnected-(U2-NC-Pad33)") (class "Default")
      (node (ref "U2") (pin "33") (pinfunction "NC_33") (pintype "passive+no_connect"))
    )
    (net (code "68") (name "unconnected-(U2-NC-Pad34)") (class "Default")
      (node (ref "U2") (pin "34") (pinfunction "NC_34") (pintype "passive+no_connect"))
    )
    (net (code "69") (name "unconnected-(U2-RA4-Pad23)") (class "Default")
      (node (ref "U2") (pin "23") (pinfunction "RA4_23") (pintype "bidirectional+no_connect"))
    )
    (net (code "70") (name "unconnected-(U2-RA5-Pad24)") (class "Default")
      (node (ref "U2") (pin "24") (pinfunction "RA5_24") (pintype "bidirectional+no_connect"))
    )
    (net (code "71") (name "unconnected-(U2-RB0-Pad8)") (class "Default")
      (node (ref "U2") (pin "8") (pinfunction "RB0_8") (pintype "bidirectional+no_connect"))
    )
    (net (code "72") (name "unconnected-(U2-RB1-Pad9)") (class "Default")
      (node (ref "U2") (pin "9") (pinfunction "RB1_9") (pintype "bidirectional+no_connect"))
    )
    (net (code "73") (name "unconnected-(U2-RB2-Pad10)") (class "Default")
      (node (ref "U2") (pin "10") (pinfunction "RB2_10") (pintype "bidirectional+no_connect"))
    )
    (net (code "74") (name "unconnected-(U2-RB3-Pad11)") (class "Default")
      (node (ref "U2") (pin "11") (pinfunction "RB3_11") (pintype "bidirectional+no_connect"))
    )
    (net (code "75") (name "unconnected-(U2-RC3-Pad37)") (class "Default")
      (node (ref "U2") (pin "37") (pinfunction "RC3_37") (pintype "bidirectional+no_connect"))
    )
    (net (code "76") (name "unconnected-(U2-RC4-Pad42)") (class "Default")
      (node (ref "U2") (pin "42") (pinfunction "RC4_42") (pintype "bidirectional+no_connect"))
    )
    (net (code "77") (name "unconnected-(U2-RC5-Pad43)") (class "Default")
      (node (ref "U2") (pin "43") (pinfunction "RC5_43") (pintype "bidirectional+no_connect"))
    )
    (net (code "78") (name "unconnected-(U2-RC6-Pad44)") (class "Default")
      (node (ref "U2") (pin "44") (pinfunction "RC6_44") (pintype "bidirectional+no_connect"))
    )
    (net (code "79") (name "unconnected-(U2-RC7-Pad1)") (class "Default")
      (node (ref "U2") (pin "1") (pinfunction "RC7_1") (pintype "bidirectional+no_connect"))
    )
    (net (code "80") (name "unconnected-(U2-RD6-Pad4)") (class "Default")
      (node (ref "U2") (pin "4") (pinfunction "RD6_4") (pintype "bidirectional+no_connect"))
    )
    (net (code "81") (name "unconnected-(U2-RD7-Pad5)") (class "Default")
      (node (ref "U2") (pin "5") (pinfunction "RD7_5") (pintype "bidirectional+no_connect"))
    )
    (net (code "82") (name "unconnected-(U2-RE0-Pad25)") (class "Default")
      (node (ref "U2") (pin "25") (pinfunction "RE0_25") (pintype "bidirectional+no_connect"))
    )
    (net (code "83") (name "unconnected-(U2-RE1-Pad26)") (class "Default")
      (node (ref "U2") (pin "26") (pinfunction "RE1_26") (pintype "bidirectional+no_connect"))
    )
    (net (code "84") (name "unconnected-(U2-RE2-Pad27)") (class "Default")
      (node (ref "U2") (pin "27") (pinfunction "RE2_27") (pintype "bidirectional+no_connect"))
    )
    (net (code "85") (name "unconnected-(U4-4A-Pad12)") (class "Default")
      (node (ref "U4") (pin "12") (pinfunction "4A_12") (pintype "input+no_connect"))
    )
    (net (code "86") (name "unconnected-(U4-4B-Pad13)") (class "Default")
      (node (ref "U4") (pin "13") (pinfunction "4B_13") (pintype "input+no_connect"))
    )
    (net (code "87") (name "unconnected-(U4-4Y-Pad11)") (class "Default")
      (node (ref "U4") (pin "11") (pinfunction "4Y_11") (pintype "output+no_connect"))
    )
  )
)
